# BpodMainBoard_r1_0.net
KiCad netlist of a schematic drawn in EAGLE
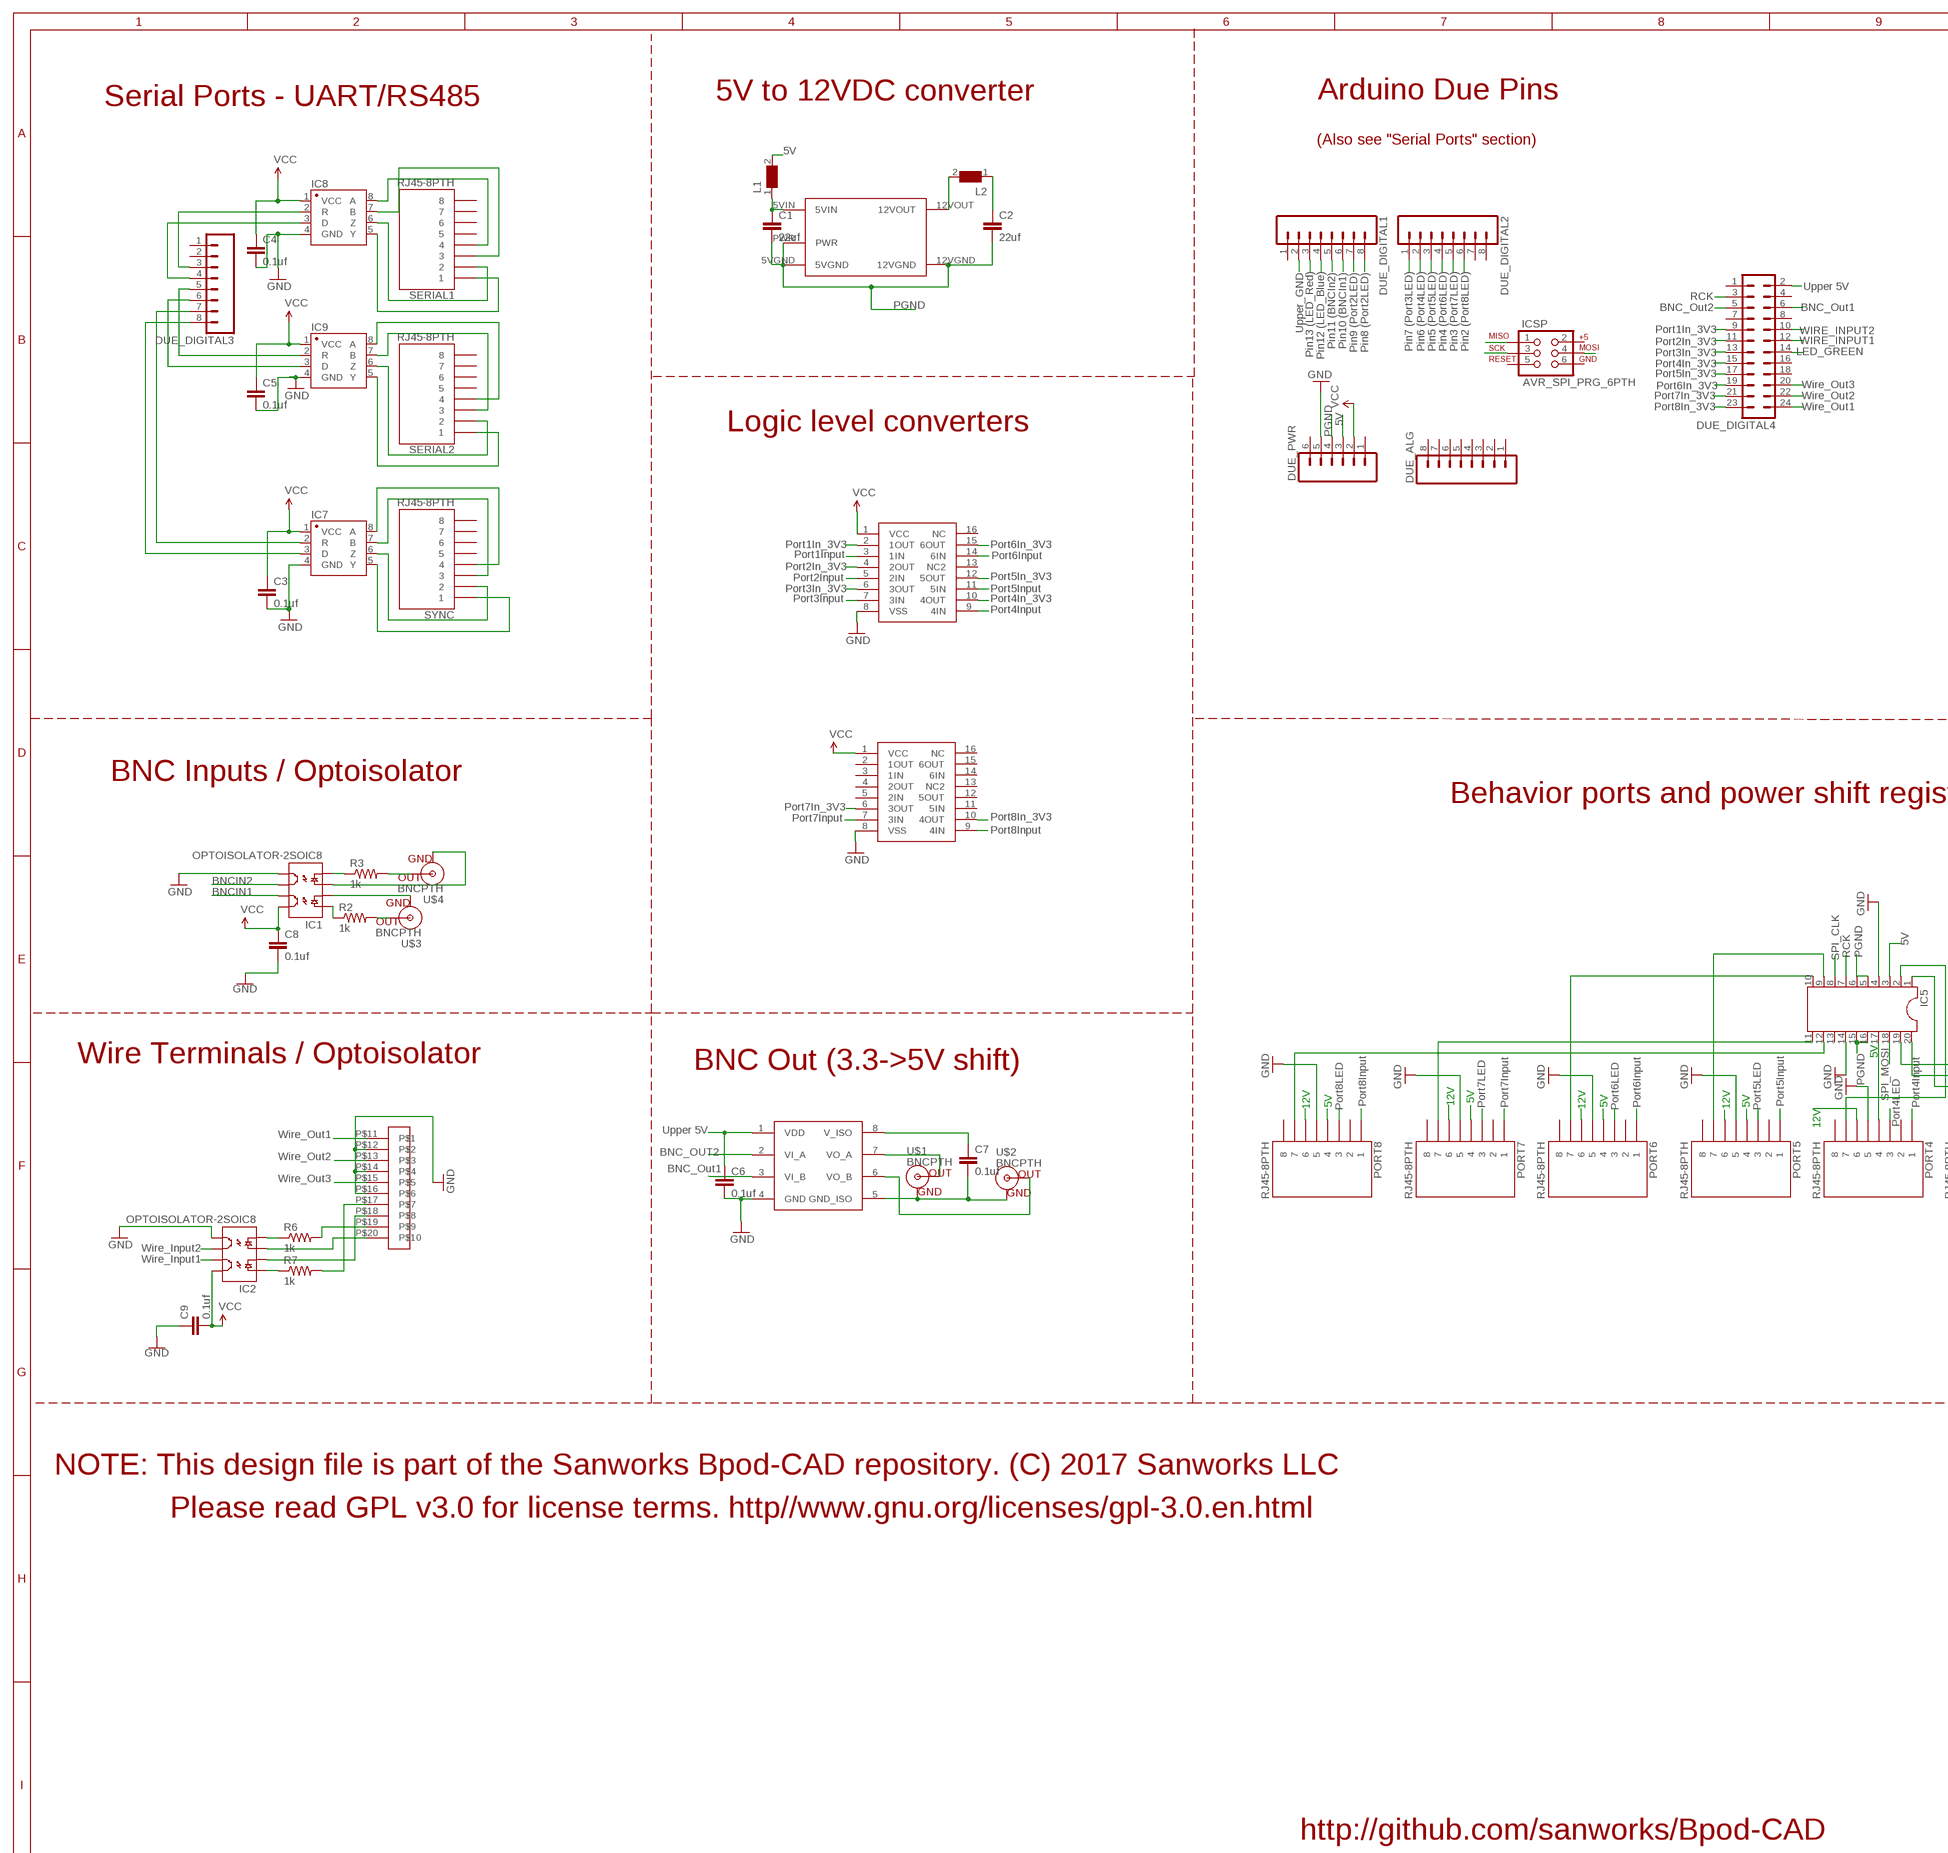
[diagram p0: schematic, sheet 1, part 1 of 2]
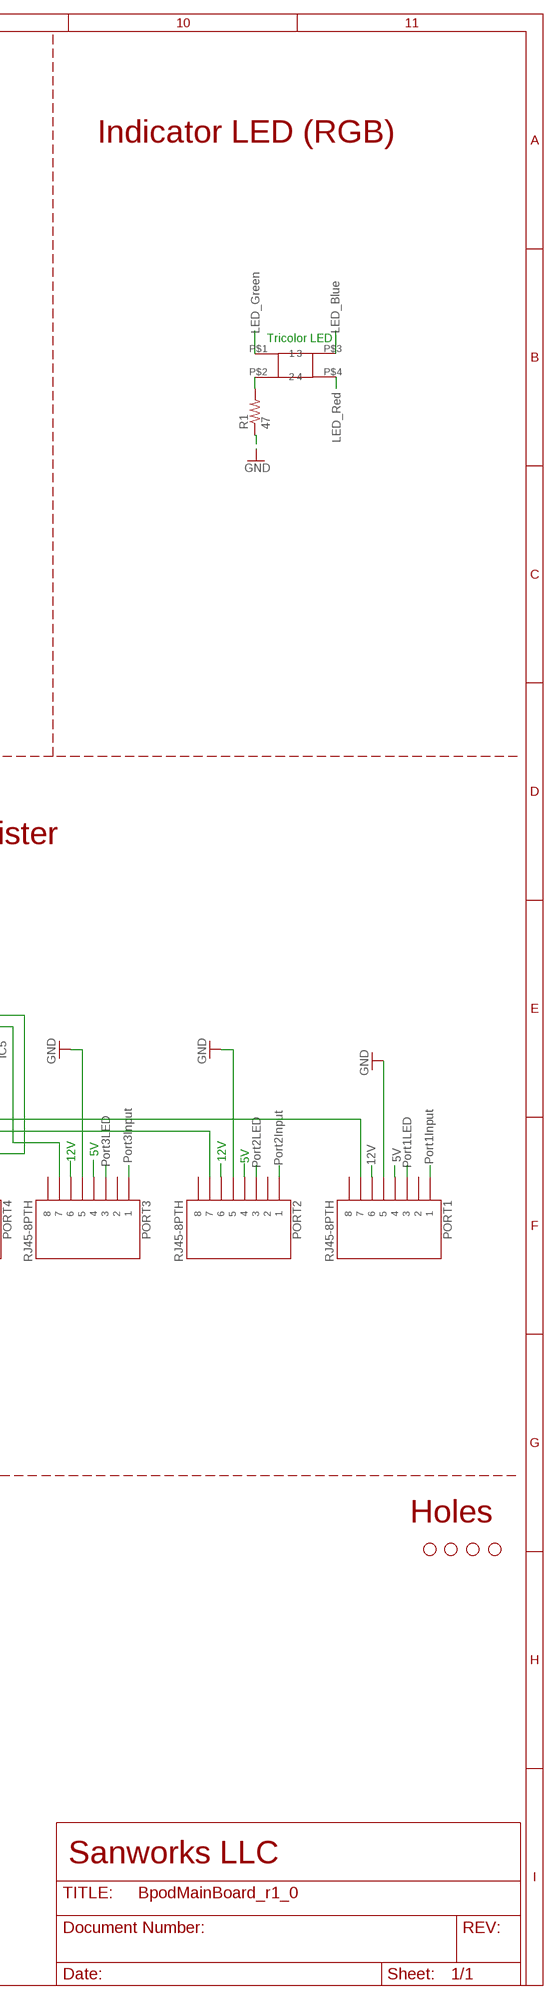
[diagram p1: schematic, sheet 1, part 2 of 2]

(export (version "E")
  (design (tool "Eeschema 10.0.6"))
  (components
    (comp (ref "C1")
      (value "22uf")
      (footprint "eagle-import:1206")
      (libsource (lib "eagle-import") (part "CAP1206"))
    )
    (comp (ref "C2")
      (value "22uf")
      (footprint "eagle-import:1206")
      (libsource (lib "eagle-import") (part "CAP1206"))
    )
    (comp (ref "C3")
      (value "0.1uf")
      (footprint "eagle-import:1206")
      (libsource (lib "eagle-import") (part "CAP1206"))
    )
    (comp (ref "C4")
      (value "0.1uf")
      (footprint "eagle-import:1206")
      (libsource (lib "eagle-import") (part "CAP1206"))
    )
    (comp (ref "C5")
      (value "0.1uf")
      (footprint "eagle-import:1206")
      (libsource (lib "eagle-import") (part "CAP1206"))
    )
    (comp (ref "C6")
      (value "0.1uf")
      (footprint "eagle-import:1206")
      (libsource (lib "eagle-import") (part "CAP1206"))
    )
    (comp (ref "C7")
      (value "0.1uf")
      (footprint "eagle-import:1206")
      (libsource (lib "eagle-import") (part "CAP1206"))
    )
    (comp (ref "C8")
      (value "0.1uf")
      (footprint "eagle-import:1206")
      (libsource (lib "eagle-import") (part "CAP1206"))
    )
    (comp (ref "C9")
      (value "0.1uf")
      (footprint "eagle-import:1206")
      (libsource (lib "eagle-import") (part "CAP1206"))
    )
    (comp (ref "DUE_ALG")
      (value "M081X08")
      (footprint "eagle-import:1X08")
      (libsource (lib "eagle-import") (part "M081X08"))
    )
    (comp (ref "DUE_DIGITAL1")
      (value "M081X08")
      (footprint "eagle-import:1X08")
      (libsource (lib "eagle-import") (part "M081X08"))
    )
    (comp (ref "DUE_DIGITAL2")
      (value "M081X08")
      (footprint "eagle-import:1X08")
      (libsource (lib "eagle-import") (part "M081X08"))
    )
    (comp (ref "DUE_DIGITAL3")
      (value "M081X08")
      (footprint "eagle-import:1X08")
      (libsource (lib "eagle-import") (part "M081X08"))
    )
    (comp (ref "DUE_DIGITAL4")
      (value "MA12-2")
      (footprint "eagle-import:MA12-2")
      (libsource (lib "eagle-import") (part "MA12-2"))
    )
    (comp (ref "DUE_PWR")
      (value "M06SIP")
      (footprint "eagle-import:1X06")
      (libsource (lib "eagle-import") (part "M06SIP"))
    )
    (comp (ref "IC1")
      (value "OPTOISOLATOR-2SOIC8")
      (footprint "eagle-import:SO08-2")
      (libsource (lib "eagle-import") (part "OPTOISOLATOR-2SOIC8"))
    )
    (comp (ref "IC2")
      (value "OPTOISOLATOR-2SOIC8")
      (footprint "eagle-import:SO08-2")
      (fields (field (name "PROD_ID") "IC-09076"))
      (libsource (lib "eagle-import") (part "OPTOISOLATOR-2SOIC8"))
    )
    (comp (ref "IC3")
      (value "CD4050")
      (footprint "eagle-import:SO16")
      (libsource (lib "eagle-import") (part "CD4050"))
    )
    (comp (ref "IC4")
      (value "CD4050")
      (footprint "eagle-import:SO16")
      (libsource (lib "eagle-import") (part "CD4050"))
    )
    (comp (ref "IC5")
      (value "DIL20")
      (footprint "eagle-import:DIL20")
      (libsource (lib "eagle-import") (part "DIL20"))
    )
    (comp (ref "IC7")
      (value "SN65HVD31DR")
      (footprint "eagle-import:SO08")
      (libsource (lib "eagle-import") (part "SN65HVD31DR"))
    )
    (comp (ref "IC8")
      (value "SN65HVD31DR")
      (footprint "eagle-import:SO08")
      (libsource (lib "eagle-import") (part "SN65HVD31DR"))
    )
    (comp (ref "IC9")
      (value "SN65HVD31DR")
      (footprint "eagle-import:SO08")
      (libsource (lib "eagle-import") (part "SN65HVD31DR"))
    )
    (comp (ref "IC10")
      (value "ADUM5240")
      (footprint "eagle-import:SO08")
      (libsource (lib "eagle-import") (part "ADUM5240"))
    )
    (comp (ref "ICSP")
      (value "AVR_SPI_PRG_6PTH")
      (footprint "eagle-import:2X3")
      (libsource (lib "eagle-import") (part "AVR_SPI_PRG_6PTH"))
    )
    (comp (ref "JP1")
      (value "STAND-OFF")
      (footprint "eagle-import:STAND-OFF")
      (libsource (lib "eagle-import") (part "STAND-OFF"))
    )
    (comp (ref "JP2")
      (value "STAND-OFF")
      (footprint "eagle-import:STAND-OFF")
      (libsource (lib "eagle-import") (part "STAND-OFF"))
    )
    (comp (ref "JP3")
      (value "STAND-OFF")
      (footprint "eagle-import:STAND-OFF")
      (libsource (lib "eagle-import") (part "STAND-OFF"))
    )
    (comp (ref "JP4")
      (value "STAND-OFF")
      (footprint "eagle-import:STAND-OFF")
      (libsource (lib "eagle-import") (part "STAND-OFF"))
    )
    (comp (ref "L1")
      (value "WE-CBF-742792118_1206")
      (footprint "eagle-import:1206")
      (fields (field (name "MPN") "742792118"))
      (libsource (lib "eagle-import") (part "WE-CBF_1206-742792118"))
    )
    (comp (ref "L2")
      (value "WE-CBF-742792118_1206")
      (footprint "eagle-import:1206")
      (fields
        (field (name "MPN") "742792118")
        (field (name "MPN_1") "742792118")
        (field (name "OC_FARNELL") "1800374")
        (field (name "OC_NEWARK") "78R5648")
        (field (name "PACKAGE") "IND-1206")
        (field (name "SUPPLIER") "Wuerth Elektronik")
      )
      (libsource (lib "eagle-import") (part "WE-CBF_1206-742792118"))
    )
    (comp (ref "PORT1")
      (value "RJ45-8PTH")
      (footprint "eagle-import:RJ45-8")
      (libsource (lib "eagle-import") (part "RJ45-8PTH"))
    )
    (comp (ref "PORT2")
      (value "RJ45-8PTH")
      (footprint "eagle-import:RJ45-8")
      (libsource (lib "eagle-import") (part "RJ45-8PTH"))
    )
    (comp (ref "PORT3")
      (value "RJ45-8PTH")
      (footprint "eagle-import:RJ45-8")
      (libsource (lib "eagle-import") (part "RJ45-8PTH"))
    )
    (comp (ref "PORT4")
      (value "RJ45-8PTH")
      (footprint "eagle-import:RJ45-8")
      (libsource (lib "eagle-import") (part "RJ45-8PTH"))
    )
    (comp (ref "PORT5")
      (value "RJ45-8PTH")
      (footprint "eagle-import:RJ45-8")
      (libsource (lib "eagle-import") (part "RJ45-8PTH"))
    )
    (comp (ref "PORT6")
      (value "RJ45-8PTH")
      (footprint "eagle-import:RJ45-8")
      (libsource (lib "eagle-import") (part "RJ45-8PTH"))
    )
    (comp (ref "PORT7")
      (value "RJ45-8PTH")
      (footprint "eagle-import:RJ45-8")
      (libsource (lib "eagle-import") (part "RJ45-8PTH"))
    )
    (comp (ref "PORT8")
      (value "RJ45-8PTH")
      (footprint "eagle-import:RJ45-8")
      (libsource (lib "eagle-import") (part "RJ45-8PTH"))
    )
    (comp (ref "R1")
      (value "47")
      (footprint "eagle-import:1206")
      (libsource (lib "eagle-import") (part "RESISTOR1206"))
    )
    (comp (ref "R2")
      (value "1k")
      (footprint "eagle-import:1206")
      (libsource (lib "eagle-import") (part "SparkFun-Resistors_RESISTOR1206"))
    )
    (comp (ref "R3")
      (value "1k")
      (footprint "eagle-import:1206")
      (libsource (lib "eagle-import") (part "SparkFun-Resistors_RESISTOR1206"))
    )
    (comp (ref "R6")
      (value "1k")
      (footprint "eagle-import:1206")
      (libsource (lib "eagle-import") (part "SparkFun-Resistors_RESISTOR1206"))
    )
    (comp (ref "R7")
      (value "1k")
      (footprint "eagle-import:1206")
      (libsource (lib "eagle-import") (part "SparkFun-Resistors_RESISTOR1206"))
    )
    (comp (ref "SERIAL1")
      (value "RJ45-8PTH")
      (footprint "eagle-import:RJ45-8")
      (libsource (lib "eagle-import") (part "RJ45-8PTH"))
    )
    (comp (ref "SERIAL2")
      (value "RJ45-8PTH")
      (footprint "eagle-import:RJ45-8")
      (libsource (lib "eagle-import") (part "RJ45-8PTH"))
    )
    (comp (ref "SYNC")
      (value "RJ45-8PTH")
      (footprint "eagle-import:RJ45-8")
      (libsource (lib "eagle-import") (part "RJ45-8PTH"))
    )
    (comp (ref "U$1")
      (value "BNCPTH")
      (footprint "eagle-import:BNC")
      (libsource (lib "eagle-import") (part "SparkFun-Connectors_BNCPTH"))
    )
    (comp (ref "U$2")
      (value "BNCPTH")
      (footprint "eagle-import:BNC")
      (libsource (lib "eagle-import") (part "SparkFun-Connectors_BNCPTH"))
    )
    (comp (ref "U$3")
      (value "BNCPTH")
      (footprint "eagle-import:BNC")
      (libsource (lib "eagle-import") (part "BNCPTH"))
    )
    (comp (ref "U$4")
      (value "BNCPTH")
      (footprint "eagle-import:BNC")
      (libsource (lib "eagle-import") (part "BNCPTH"))
    )
    (comp (ref "U$5")
      (value "TDK_LAMBDA_5V_TO_12V")
      (footprint "eagle-import:TDK_LAMBDA_5V_12V")
      (libsource (lib "eagle-import") (part "TDK_LAMBDA_5V_TO_12V"))
    )
    (comp (ref "U$6")
      (value "10POS_SPRING_TERMINAL")
      (footprint "eagle-import:10POS_SCREW_TERMINAL")
      (libsource (lib "eagle-import") (part "10POS_SPRING_TERMINAL"))
    )
    (comp (ref "U$8")
      (value "SQUARE_TRICOLOR_LED")
      (footprint "eagle-import:SQUARE_TRICOLOR_LED")
      (libsource (lib "eagle-import") (part "SQUARE_TRICOLOR_LED"))
    )
  )
  (nets
    (net (code "1") (name "/5V") (class "Default")
      (node (ref "DUE_PWR") (pin "3") (pinfunction "3_3") (pintype "passive"))
      (node (ref "IC5") (pin "17") (pinfunction "17_17") (pintype "passive"))
      (node (ref "IC5") (pin "3") (pinfunction "3_3") (pintype "passive"))
      (node (ref "L1") (pin "2") (pinfunction "2_2") (pintype "passive"))
      (node (ref "PORT1") (pin "4") (pinfunction "4_4") (pintype "bidirectional"))
      (node (ref "PORT2") (pin "4") (pinfunction "4_4") (pintype "bidirectional"))
      (node (ref "PORT3") (pin "4") (pinfunction "4_4") (pintype "bidirectional"))
      (node (ref "PORT4") (pin "4") (pinfunction "4_4") (pintype "bidirectional"))
      (node (ref "PORT5") (pin "4") (pinfunction "4_4") (pintype "bidirectional"))
      (node (ref "PORT6") (pin "4") (pinfunction "4_4") (pintype "bidirectional"))
      (node (ref "PORT7") (pin "4") (pinfunction "4_4") (pintype "bidirectional"))
      (node (ref "PORT8") (pin "4") (pinfunction "4_4") (pintype "bidirectional"))
    )
    (net (code "2") (name "/12V") (class "Default")
      (node (ref "C2") (pin "1") (pinfunction "1_1") (pintype "passive"))
      (node (ref "L2") (pin "1") (pinfunction "1_1") (pintype "passive"))
      (node (ref "PORT1") (pin "6") (pinfunction "6_6") (pintype "bidirectional"))
      (node (ref "PORT2") (pin "6") (pinfunction "6_6") (pintype "bidirectional"))
      (node (ref "PORT3") (pin "6") (pinfunction "6_6") (pintype "bidirectional"))
      (node (ref "PORT4") (pin "6") (pinfunction "6_6") (pintype "bidirectional"))
      (node (ref "PORT5") (pin "6") (pinfunction "6_6") (pintype "bidirectional"))
      (node (ref "PORT6") (pin "6") (pinfunction "6_6") (pintype "bidirectional"))
      (node (ref "PORT7") (pin "6") (pinfunction "6_6") (pintype "bidirectional"))
      (node (ref "PORT8") (pin "6") (pinfunction "6_6") (pintype "bidirectional"))
    )
    (net (code "3") (name "/BNCIN1") (class "Default")
      (node (ref "DUE_DIGITAL1") (pin "6") (pinfunction "6_6") (pintype "passive"))
      (node (ref "IC1") (pin "7") (pinfunction "EM1_7") (pintype "bidirectional"))
    )
    (net (code "4") (name "/BNCIN2") (class "Default")
      (node (ref "DUE_DIGITAL1") (pin "5") (pinfunction "5_5") (pintype "passive"))
      (node (ref "IC1") (pin "6") (pinfunction "CL2_6") (pintype "bidirectional"))
    )
    (net (code "5") (name "/BNC_OUT1") (class "Default")
      (node (ref "DUE_DIGITAL4") (pin "6") (pinfunction "6_6") (pintype "passive"))
      (node (ref "IC10") (pin "3") (pinfunction "VI_B_3") (pintype "bidirectional"))
    )
    (net (code "6") (name "/BNC_OUT2") (class "Default")
      (node (ref "DUE_DIGITAL4") (pin "5") (pinfunction "5_5") (pintype "passive"))
      (node (ref "IC10") (pin "2") (pinfunction "VI_A_2") (pintype "bidirectional"))
    )
    (net (code "7") (name "/LED_BLUE") (class "Default")
      (node (ref "DUE_DIGITAL1") (pin "4") (pinfunction "4_4") (pintype "passive"))
      (node (ref "U$8") (pin "P$3") (pinfunction "3_P$3") (pintype "bidirectional"))
    )
    (net (code "8") (name "/LED_GREEN") (class "Default")
      (node (ref "DUE_DIGITAL4") (pin "14") (pinfunction "14_14") (pintype "passive"))
      (node (ref "U$8") (pin "P$1") (pinfunction "1_P$1") (pintype "bidirectional"))
    )
    (net (code "9") (name "/LED_RED") (class "Default")
      (node (ref "DUE_DIGITAL1") (pin "3") (pinfunction "3_3") (pintype "passive"))
      (node (ref "U$8") (pin "P$4") (pinfunction "4_P$4") (pintype "bidirectional"))
    )
    (net (code "10") (name "/MOSI") (class "Default")
      (node (ref "IC5") (pin "18") (pinfunction "18_18") (pintype "passive"))
      (node (ref "ICSP") (pin "4") (pinfunction "4_4") (pintype "passive"))
    )
    (net (code "11") (name "/PGND") (class "Default")
      (node (ref "C1") (pin "2") (pinfunction "2_2") (pintype "passive"))
      (node (ref "C2") (pin "2") (pinfunction "2_2") (pintype "passive"))
      (node (ref "DUE_PWR") (pin "4") (pinfunction "4_4") (pintype "passive"))
      (node (ref "IC5") (pin "15") (pinfunction "15_15") (pintype "passive"))
      (node (ref "IC5") (pin "16") (pinfunction "16_16") (pintype "passive"))
      (node (ref "IC5") (pin "5") (pinfunction "5_5") (pintype "passive"))
      (node (ref "IC5") (pin "6") (pinfunction "6_6") (pintype "passive"))
      (node (ref "U$5") (pin "12VGND") (pinfunction "12VGND_12VGND") (pintype "bidirectional"))
      (node (ref "U$5") (pin "5VGND") (pinfunction "5VGND_5VGND") (pintype "bidirectional"))
      (node (ref "U$5") (pin "PWR") (pinfunction "PWR_PWR") (pintype "bidirectional"))
    )
    (net (code "12") (name "/PORT1INPUT") (class "Default")
      (node (ref "IC3") (pin "3") (pinfunction "1IN_3") (pintype "bidirectional"))
      (node (ref "PORT1") (pin "1") (pinfunction "1_1") (pintype "bidirectional"))
    )
    (net (code "13") (name "/PORT1IN_3V3") (class "Default")
      (node (ref "DUE_DIGITAL4") (pin "9") (pinfunction "9_9") (pintype "passive"))
      (node (ref "IC3") (pin "2") (pinfunction "1OUT_2") (pintype "bidirectional"))
    )
    (net (code "14") (name "/PORT1LED") (class "Default")
      (node (ref "DUE_DIGITAL1") (pin "7") (pinfunction "7_7") (pintype "passive"))
      (node (ref "PORT1") (pin "3") (pinfunction "3_3") (pintype "bidirectional"))
    )
    (net (code "15") (name "/PORT2INPUT") (class "Default")
      (node (ref "IC3") (pin "5") (pinfunction "2IN_5") (pintype "bidirectional"))
      (node (ref "PORT2") (pin "1") (pinfunction "1_1") (pintype "bidirectional"))
    )
    (net (code "16") (name "/PORT2IN_3V3") (class "Default")
      (node (ref "DUE_DIGITAL4") (pin "11") (pinfunction "11_11") (pintype "passive"))
      (node (ref "IC3") (pin "4") (pinfunction "2OUT_4") (pintype "bidirectional"))
    )
    (net (code "17") (name "/PORT2LED") (class "Default")
      (node (ref "DUE_DIGITAL1") (pin "8") (pinfunction "8_8") (pintype "passive"))
      (node (ref "PORT2") (pin "3") (pinfunction "3_3") (pintype "bidirectional"))
    )
    (net (code "18") (name "/PORT3INPUT") (class "Default")
      (node (ref "IC3") (pin "7") (pinfunction "3IN_7") (pintype "bidirectional"))
      (node (ref "PORT3") (pin "1") (pinfunction "1_1") (pintype "bidirectional"))
    )
    (net (code "19") (name "/PORT3IN_3V3") (class "Default")
      (node (ref "DUE_DIGITAL4") (pin "13") (pinfunction "13_13") (pintype "passive"))
      (node (ref "IC3") (pin "6") (pinfunction "3OUT_6") (pintype "bidirectional"))
    )
    (net (code "20") (name "/PORT3LED") (class "Default")
      (node (ref "DUE_DIGITAL2") (pin "1") (pinfunction "1_1") (pintype "passive"))
      (node (ref "PORT3") (pin "3") (pinfunction "3_3") (pintype "bidirectional"))
    )
    (net (code "21") (name "/PORT4INPUT") (class "Default")
      (node (ref "IC3") (pin "9") (pinfunction "4IN_9") (pintype "bidirectional"))
      (node (ref "PORT4") (pin "1") (pinfunction "1_1") (pintype "bidirectional"))
    )
    (net (code "22") (name "/PORT4IN_3V3") (class "Default")
      (node (ref "DUE_DIGITAL4") (pin "15") (pinfunction "15_15") (pintype "passive"))
      (node (ref "IC3") (pin "10") (pinfunction "4OUT_10") (pintype "bidirectional"))
    )
    (net (code "23") (name "/PORT4LED") (class "Default")
      (node (ref "DUE_DIGITAL2") (pin "2") (pinfunction "2_2") (pintype "passive"))
      (node (ref "PORT4") (pin "3") (pinfunction "3_3") (pintype "bidirectional"))
    )
    (net (code "24") (name "/PORT5INPUT") (class "Default")
      (node (ref "IC3") (pin "11") (pinfunction "5IN_11") (pintype "bidirectional"))
      (node (ref "PORT5") (pin "1") (pinfunction "1_1") (pintype "bidirectional"))
    )
    (net (code "25") (name "/PORT5IN_3V3") (class "Default")
      (node (ref "DUE_DIGITAL4") (pin "17") (pinfunction "17_17") (pintype "passive"))
      (node (ref "IC3") (pin "12") (pinfunction "5OUT_12") (pintype "bidirectional"))
    )
    (net (code "26") (name "/PORT5LED") (class "Default")
      (node (ref "DUE_DIGITAL2") (pin "3") (pinfunction "3_3") (pintype "passive"))
      (node (ref "PORT5") (pin "3") (pinfunction "3_3") (pintype "bidirectional"))
    )
    (net (code "27") (name "/PORT6INPUT") (class "Default")
      (node (ref "IC3") (pin "14") (pinfunction "6IN_14") (pintype "bidirectional"))
      (node (ref "PORT6") (pin "1") (pinfunction "1_1") (pintype "bidirectional"))
    )
    (net (code "28") (name "/PORT6IN_3V3") (class "Default")
      (node (ref "DUE_DIGITAL4") (pin "19") (pinfunction "19_19") (pintype "passive"))
      (node (ref "IC3") (pin "15") (pinfunction "6OUT_15") (pintype "bidirectional"))
    )
    (net (code "29") (name "/PORT6LED") (class "Default")
      (node (ref "DUE_DIGITAL2") (pin "4") (pinfunction "4_4") (pintype "passive"))
      (node (ref "PORT6") (pin "3") (pinfunction "3_3") (pintype "bidirectional"))
    )
    (net (code "30") (name "/PORT7INPUT") (class "Default")
      (node (ref "IC4") (pin "7") (pinfunction "3IN_7") (pintype "bidirectional"))
      (node (ref "PORT7") (pin "1") (pinfunction "1_1") (pintype "bidirectional"))
    )
    (net (code "31") (name "/PORT7IN_3V3") (class "Default")
      (node (ref "DUE_DIGITAL4") (pin "21") (pinfunction "21_21") (pintype "passive"))
      (node (ref "IC4") (pin "6") (pinfunction "3OUT_6") (pintype "bidirectional"))
    )
    (net (code "32") (name "/PORT7LED") (class "Default")
      (node (ref "DUE_DIGITAL2") (pin "5") (pinfunction "5_5") (pintype "passive"))
      (node (ref "PORT7") (pin "3") (pinfunction "3_3") (pintype "bidirectional"))
    )
    (net (code "33") (name "/PORT8INPUT") (class "Default")
      (node (ref "IC4") (pin "9") (pinfunction "4IN_9") (pintype "bidirectional"))
      (node (ref "PORT8") (pin "1") (pinfunction "1_1") (pintype "bidirectional"))
    )
    (net (code "34") (name "/PORT8IN_3V3") (class "Default")
      (node (ref "DUE_DIGITAL4") (pin "23") (pinfunction "23_23") (pintype "passive"))
      (node (ref "IC4") (pin "10") (pinfunction "4OUT_10") (pintype "bidirectional"))
    )
    (net (code "35") (name "/PORT8LED") (class "Default")
      (node (ref "DUE_DIGITAL2") (pin "6") (pinfunction "6_6") (pintype "passive"))
      (node (ref "PORT8") (pin "3") (pinfunction "3_3") (pintype "bidirectional"))
    )
    (net (code "36") (name "/RCK") (class "Default")
      (node (ref "DUE_DIGITAL4") (pin "3") (pinfunction "3_3") (pintype "passive"))
      (node (ref "IC5") (pin "7") (pinfunction "7_7") (pintype "passive"))
    )
    (net (code "37") (name "/SPI_CLK") (class "Default")
      (node (ref "IC5") (pin "8") (pinfunction "8_8") (pintype "passive"))
      (node (ref "ICSP") (pin "3") (pinfunction "3_3") (pintype "passive"))
    )
    (net (code "38") (name "/UPPER_5V") (class "Default")
      (node (ref "C6") (pin "1") (pinfunction "1_1") (pintype "passive"))
      (node (ref "DUE_DIGITAL4") (pin "2") (pinfunction "2_2") (pintype "passive"))
      (node (ref "IC10") (pin "1") (pinfunction "VDD_1") (pintype "bidirectional"))
    )
    (net (code "39") (name "/WIREOUT3") (class "Default")
      (node (ref "DUE_DIGITAL4") (pin "20") (pinfunction "20_20") (pintype "passive"))
      (node (ref "U$6") (pin "P$15") (pinfunction "P$5_P$15") (pintype "bidirectional"))
    )
    (net (code "40") (name "/WIRE_INPUT1") (class "Default")
      (node (ref "DUE_DIGITAL4") (pin "12") (pinfunction "12_12") (pintype "passive"))
      (node (ref "IC2") (pin "7") (pinfunction "EM1_7") (pintype "bidirectional"))
    )
    (net (code "41") (name "/WIRE_INPUT2") (class "Default")
      (node (ref "DUE_DIGITAL4") (pin "10") (pinfunction "10_10") (pintype "passive"))
      (node (ref "IC2") (pin "6") (pinfunction "CL2_6") (pintype "bidirectional"))
    )
    (net (code "42") (name "/WIRE_OUT1") (class "Default")
      (node (ref "DUE_DIGITAL4") (pin "24") (pinfunction "24_24") (pintype "passive"))
      (node (ref "U$6") (pin "P$11") (pinfunction "P$1_P$11") (pintype "bidirectional"))
    )
    (net (code "43") (name "/WIRE_OUT2") (class "Default")
      (node (ref "DUE_DIGITAL4") (pin "22") (pinfunction "22_22") (pintype "passive"))
      (node (ref "U$6") (pin "P$13") (pinfunction "P$3_P$13") (pintype "bidirectional"))
    )
    (net (code "44") (name "GND") (class "Default")
      (node (ref "C3") (pin "2") (pinfunction "2_2") (pintype "passive"))
      (node (ref "C4") (pin "2") (pinfunction "2_2") (pintype "passive"))
      (node (ref "C5") (pin "2") (pinfunction "2_2") (pintype "passive"))
      (node (ref "C6") (pin "2") (pinfunction "2_2") (pintype "passive"))
      (node (ref "C8") (pin "2") (pinfunction "2_2") (pintype "passive"))
      (node (ref "C9") (pin "1") (pinfunction "1_1") (pintype "passive"))
      (node (ref "DUE_PWR") (pin "5") (pinfunction "5_5") (pintype "passive"))
      (node (ref "IC1") (pin "5") (pinfunction "EM2_5") (pintype "bidirectional"))
      (node (ref "IC10") (pin "4") (pinfunction "GND_4") (pintype "bidirectional"))
      (node (ref "IC2") (pin "5") (pinfunction "EM2_5") (pintype "bidirectional"))
      (node (ref "IC3") (pin "8") (pinfunction "VSS_8") (pintype "bidirectional"))
      (node (ref "IC4") (pin "8") (pinfunction "VSS_8") (pintype "bidirectional"))
      (node (ref "IC5") (pin "14") (pinfunction "14_14") (pintype "passive"))
      (node (ref "IC5") (pin "4") (pinfunction "4_4") (pintype "passive"))
      (node (ref "IC7") (pin "4") (pinfunction "GND_4") (pintype "bidirectional"))
      (node (ref "IC8") (pin "4") (pinfunction "GND_4") (pintype "bidirectional"))
      (node (ref "IC9") (pin "4") (pinfunction "GND_4") (pintype "bidirectional"))
      (node (ref "PORT1") (pin "5") (pinfunction "5_5") (pintype "bidirectional"))
      (node (ref "PORT2") (pin "5") (pinfunction "5_5") (pintype "bidirectional"))
      (node (ref "PORT3") (pin "5") (pinfunction "5_5") (pintype "bidirectional"))
      (node (ref "PORT4") (pin "5") (pinfunction "5_5") (pintype "bidirectional"))
      (node (ref "PORT5") (pin "5") (pinfunction "5_5") (pintype "bidirectional"))
      (node (ref "PORT6") (pin "5") (pinfunction "5_5") (pintype "bidirectional"))
      (node (ref "PORT7") (pin "5") (pinfunction "5_5") (pintype "bidirectional"))
      (node (ref "PORT8") (pin "5") (pinfunction "5_5") (pintype "bidirectional"))
      (node (ref "R1") (pin "1") (pinfunction "1_1") (pintype "passive"))
      (node (ref "U$6") (pin "P$12") (pinfunction "P$2_P$12") (pintype "bidirectional"))
      (node (ref "U$6") (pin "P$14") (pinfunction "P$4_P$14") (pintype "bidirectional"))
      (node (ref "U$6") (pin "P$16") (pinfunction "P$6_P$16") (pintype "bidirectional"))
    )
    (net (code "45") (name "Net-(C1-Pad1)") (class "Default")
      (node (ref "C1") (pin "1") (pinfunction "1_1") (pintype "passive"))
      (node (ref "L1") (pin "1") (pinfunction "1_1") (pintype "passive"))
      (node (ref "U$5") (pin "5VIN") (pinfunction "5VIN_5VIN") (pintype "bidirectional"))
    )
    (net (code "46") (name "Net-(IC1-A1)") (class "Default")
      (node (ref "IC1") (pin "1") (pinfunction "A1_1") (pintype "bidirectional"))
      (node (ref "R2") (pin "1") (pinfunction "1_1") (pintype "passive"))
    )
    (net (code "47") (name "Net-(IC1-A2)") (class "Default")
      (node (ref "IC1") (pin "3") (pinfunction "A2_3") (pintype "bidirectional"))
      (node (ref "U$4") (pin "GND") (pinfunction "GND_GND") (pintype "bidirectional"))
    )
    (net (code "48") (name "Net-(IC1-C1)") (class "Default")
      (node (ref "IC1") (pin "2") (pinfunction "C1_2") (pintype "bidirectional"))
      (node (ref "U$3") (pin "GND") (pinfunction "GND_GND") (pintype "bidirectional"))
    )
    (net (code "49") (name "Net-(IC1-C2)") (class "Default")
      (node (ref "IC1") (pin "4") (pinfunction "C2_4") (pintype "bidirectional"))
      (node (ref "R3") (pin "1") (pinfunction "1_1") (pintype "passive"))
    )
    (net (code "50") (name "Net-(IC2-A1)") (class "Default")
      (node (ref "IC2") (pin "1") (pinfunction "A1_1") (pintype "bidirectional"))
      (node (ref "R7") (pin "1") (pinfunction "1_1") (pintype "passive"))
    )
    (net (code "51") (name "Net-(IC2-A2)") (class "Default")
      (node (ref "IC2") (pin "3") (pinfunction "A2_3") (pintype "bidirectional"))
      (node (ref "U$6") (pin "P$20") (pinfunction "P$10_P$20") (pintype "bidirectional"))
    )
    (net (code "52") (name "Net-(IC2-C1)") (class "Default")
      (node (ref "IC2") (pin "2") (pinfunction "C1_2") (pintype "bidirectional"))
      (node (ref "U$6") (pin "P$18") (pinfunction "P$8_P$18") (pintype "bidirectional"))
    )
    (net (code "53") (name "Net-(IC2-C2)") (class "Default")
      (node (ref "IC2") (pin "4") (pinfunction "C2_4") (pintype "bidirectional"))
      (node (ref "R6") (pin "1") (pinfunction "1_1") (pintype "passive"))
    )
    (net (code "54") (name "Net-(IC5-Pad1)") (class "Default")
      (node (ref "IC5") (pin "1") (pinfunction "1_1") (pintype "passive"))
      (node (ref "PORT3") (pin "7") (pinfunction "7_7") (pintype "bidirectional"))
    )
    (net (code "55") (name "Net-(IC5-Pad2)") (class "Default")
      (node (ref "IC5") (pin "2") (pinfunction "2_2") (pintype "passive"))
      (node (ref "PORT4") (pin "7") (pinfunction "7_7") (pintype "bidirectional"))
    )
    (net (code "56") (name "Net-(IC5-Pad9)") (class "Default")
      (node (ref "IC5") (pin "9") (pinfunction "9_9") (pintype "passive"))
      (node (ref "PORT5") (pin "7") (pinfunction "7_7") (pintype "bidirectional"))
    )
    (net (code "57") (name "Net-(IC5-Pad10)") (class "Default")
      (node (ref "IC5") (pin "10") (pinfunction "10_10") (pintype "passive"))
      (node (ref "PORT6") (pin "7") (pinfunction "7_7") (pintype "bidirectional"))
    )
    (net (code "58") (name "Net-(IC5-Pad11)") (class "Default")
      (node (ref "IC5") (pin "11") (pinfunction "11_11") (pintype "passive"))
      (node (ref "PORT7") (pin "7") (pinfunction "7_7") (pintype "bidirectional"))
    )
    (net (code "59") (name "Net-(IC5-Pad12)") (class "Default")
      (node (ref "IC5") (pin "12") (pinfunction "12_12") (pintype "passive"))
      (node (ref "PORT8") (pin "7") (pinfunction "7_7") (pintype "bidirectional"))
    )
    (net (code "60") (name "Net-(IC5-Pad19)") (class "Default")
      (node (ref "IC5") (pin "19") (pinfunction "19_19") (pintype "passive"))
      (node (ref "PORT1") (pin "7") (pinfunction "7_7") (pintype "bidirectional"))
    )
    (net (code "61") (name "Net-(IC5-Pad20)") (class "Default")
      (node (ref "IC5") (pin "20") (pinfunction "20_20") (pintype "passive"))
      (node (ref "PORT2") (pin "7") (pinfunction "7_7") (pintype "bidirectional"))
    )
    (net (code "62") (name "Net-(IC7-A)") (class "Default")
      (node (ref "IC7") (pin "8") (pinfunction "A_8") (pintype "bidirectional"))
      (node (ref "SYNC") (pin "4") (pinfunction "4_4") (pintype "bidirectional"))
    )
    (net (code "63") (name "Net-(IC7-B)") (class "Default")
      (node (ref "IC7") (pin "7") (pinfunction "B_7") (pintype "bidirectional"))
      (node (ref "SYNC") (pin "3") (pinfunction "3_3") (pintype "bidirectional"))
    )
    (net (code "64") (name "Net-(IC7-D)") (class "Default")
      (node (ref "DUE_DIGITAL3") (pin "8") (pinfunction "8_8") (pintype "passive"))
      (node (ref "IC7") (pin "3") (pinfunction "D_3") (pintype "bidirectional"))
    )
    (net (code "65") (name "Net-(IC7-R)") (class "Default")
      (node (ref "DUE_DIGITAL3") (pin "7") (pinfunction "7_7") (pintype "passive"))
      (node (ref "IC7") (pin "2") (pinfunction "R_2") (pintype "bidirectional"))
    )
    (net (code "66") (name "Net-(IC7-Y)") (class "Default")
      (node (ref "IC7") (pin "5") (pinfunction "Y_5") (pintype "bidirectional"))
      (node (ref "SYNC") (pin "1") (pinfunction "1_1") (pintype "bidirectional"))
    )
    (net (code "67") (name "Net-(IC7-Z)") (class "Default")
      (node (ref "IC7") (pin "6") (pinfunction "Z_6") (pintype "bidirectional"))
      (node (ref "SYNC") (pin "2") (pinfunction "2_2") (pintype "bidirectional"))
    )
    (net (code "68") (name "Net-(IC8-A)") (class "Default")
      (node (ref "IC8") (pin "8") (pinfunction "A_8") (pintype "bidirectional"))
      (node (ref "SERIAL1") (pin "4") (pinfunction "4_4") (pintype "bidirectional"))
    )
    (net (code "69") (name "Net-(IC8-B)") (class "Default")
      (node (ref "IC8") (pin "7") (pinfunction "B_7") (pintype "bidirectional"))
      (node (ref "SERIAL1") (pin "3") (pinfunction "3_3") (pintype "bidirectional"))
    )
    (net (code "70") (name "Net-(IC8-D)") (class "Default")
      (node (ref "DUE_DIGITAL3") (pin "4") (pinfunction "4_4") (pintype "passive"))
      (node (ref "IC8") (pin "3") (pinfunction "D_3") (pintype "bidirectional"))
    )
    (net (code "71") (name "Net-(IC8-R)") (class "Default")
      (node (ref "DUE_DIGITAL3") (pin "3") (pinfunction "3_3") (pintype "passive"))
      (node (ref "IC8") (pin "2") (pinfunction "R_2") (pintype "bidirectional"))
    )
    (net (code "72") (name "Net-(IC8-Y)") (class "Default")
      (node (ref "IC8") (pin "5") (pinfunction "Y_5") (pintype "bidirectional"))
      (node (ref "SERIAL1") (pin "1") (pinfunction "1_1") (pintype "bidirectional"))
    )
    (net (code "73") (name "Net-(IC8-Z)") (class "Default")
      (node (ref "IC8") (pin "6") (pinfunction "Z_6") (pintype "bidirectional"))
      (node (ref "SERIAL1") (pin "2") (pinfunction "2_2") (pintype "bidirectional"))
    )
    (net (code "74") (name "Net-(IC9-A)") (class "Default")
      (node (ref "IC9") (pin "8") (pinfunction "A_8") (pintype "bidirectional"))
      (node (ref "SERIAL2") (pin "4") (pinfunction "4_4") (pintype "bidirectional"))
    )
    (net (code "75") (name "Net-(IC9-B)") (class "Default")
      (node (ref "IC9") (pin "7") (pinfunction "B_7") (pintype "bidirectional"))
      (node (ref "SERIAL2") (pin "3") (pinfunction "3_3") (pintype "bidirectional"))
    )
    (net (code "76") (name "Net-(IC9-D)") (class "Default")
      (node (ref "DUE_DIGITAL3") (pin "6") (pinfunction "6_6") (pintype "passive"))
      (node (ref "IC9") (pin "3") (pinfunction "D_3") (pintype "bidirectional"))
    )
    (net (code "77") (name "Net-(IC9-R)") (class "Default")
      (node (ref "DUE_DIGITAL3") (pin "5") (pinfunction "5_5") (pintype "passive"))
      (node (ref "IC9") (pin "2") (pinfunction "R_2") (pintype "bidirectional"))
    )
    (net (code "78") (name "Net-(IC9-Y)") (class "Default")
      (node (ref "IC9") (pin "5") (pinfunction "Y_5") (pintype "bidirectional"))
      (node (ref "SERIAL2") (pin "1") (pinfunction "1_1") (pintype "bidirectional"))
    )
    (net (code "79") (name "Net-(IC9-Z)") (class "Default")
      (node (ref "IC9") (pin "6") (pinfunction "Z_6") (pintype "bidirectional"))
      (node (ref "SERIAL2") (pin "2") (pinfunction "2_2") (pintype "bidirectional"))
    )
    (net (code "80") (name "Net-(IC10-GND_ISO)") (class "Default")
      (node (ref "C7") (pin "2") (pinfunction "2_2") (pintype "passive"))
      (node (ref "IC10") (pin "5") (pinfunction "GND_ISO_5") (pintype "bidirectional"))
      (node (ref "U$1") (pin "GND") (pinfunction "GND_GND") (pintype "bidirectional"))
      (node (ref "U$2") (pin "GND") (pinfunction "GND_GND") (pintype "bidirectional"))
    )
    (net (code "81") (name "Net-(IC10-VO_A)") (class "Default")
      (node (ref "IC10") (pin "7") (pinfunction "VO_A_7") (pintype "bidirectional"))
      (node (ref "U$1") (pin "S") (pinfunction "OUT_S") (pintype "bidirectional"))
    )
    (net (code "82") (name "Net-(IC10-VO_B)") (class "Default")
      (node (ref "IC10") (pin "6") (pinfunction "VO_B_6") (pintype "bidirectional"))
      (node (ref "U$2") (pin "S") (pinfunction "OUT_S") (pintype "bidirectional"))
    )
    (net (code "83") (name "Net-(IC10-V_ISO)") (class "Default")
      (node (ref "C7") (pin "1") (pinfunction "1_1") (pintype "passive"))
      (node (ref "IC10") (pin "8") (pinfunction "V_ISO_8") (pintype "bidirectional"))
    )
    (net (code "84") (name "Net-(L2-Pad2)") (class "Default")
      (node (ref "L2") (pin "2") (pinfunction "2_2") (pintype "passive"))
      (node (ref "U$5") (pin "12VOUT") (pinfunction "12VOUT_12VOUT") (pintype "bidirectional"))
    )
    (net (code "85") (name "Net-(U$3-OUT)") (class "Default")
      (node (ref "R2") (pin "2") (pinfunction "2_2") (pintype "passive"))
      (node (ref "U$3") (pin "S") (pinfunction "OUT_S") (pintype "bidirectional"))
    )
    (net (code "86") (name "Net-(U$4-OUT)") (class "Default")
      (node (ref "R3") (pin "2") (pinfunction "2_2") (pintype "passive"))
      (node (ref "U$4") (pin "S") (pinfunction "OUT_S") (pintype "bidirectional"))
    )
    (net (code "87") (name "Net-(U$6-P$7)") (class "Default")
      (node (ref "R7") (pin "2") (pinfunction "2_2") (pintype "passive"))
      (node (ref "U$6") (pin "P$17") (pinfunction "P$7_P$17") (pintype "bidirectional"))
    )
    (net (code "88") (name "Net-(U$6-P$9)") (class "Default")
      (node (ref "R6") (pin "2") (pinfunction "2_2") (pintype "passive"))
      (node (ref "U$6") (pin "P$19") (pinfunction "P$9_P$19") (pintype "bidirectional"))
    )
    (net (code "89") (name "Net-(U$8-2)") (class "Default")
      (node (ref "R1") (pin "2") (pinfunction "2_2") (pintype "passive"))
      (node (ref "U$8") (pin "P$2") (pinfunction "2_P$2") (pintype "bidirectional"))
    )
    (net (code "90") (name "VCC") (class "Default")
      (node (ref "C3") (pin "1") (pinfunction "1_1") (pintype "passive"))
      (node (ref "C4") (pin "1") (pinfunction "1_1") (pintype "passive"))
      (node (ref "C5") (pin "1") (pinfunction "1_1") (pintype "passive"))
      (node (ref "C8") (pin "1") (pinfunction "1_1") (pintype "passive"))
      (node (ref "C9") (pin "2") (pinfunction "2_2") (pintype "passive"))
      (node (ref "DUE_PWR") (pin "2") (pinfunction "2_2") (pintype "passive"))
      (node (ref "IC1") (pin "8") (pinfunction "CL1_8") (pintype "bidirectional"))
      (node (ref "IC2") (pin "8") (pinfunction "CL1_8") (pintype "bidirectional"))
      (node (ref "IC3") (pin "1") (pinfunction "VCC_1") (pintype "bidirectional"))
      (node (ref "IC4") (pin "1") (pinfunction "VCC_1") (pintype "bidirectional"))
      (node (ref "IC7") (pin "1") (pinfunction "VCC_1") (pintype "bidirectional"))
      (node (ref "IC8") (pin "1") (pinfunction "VCC_1") (pintype "bidirectional"))
      (node (ref "IC9") (pin "1") (pinfunction "VCC_1") (pintype "bidirectional"))
    )
    (net (code "91") (name "unconnected-(DUE_ALG-Pad1)") (class "Default")
      (node (ref "DUE_ALG") (pin "1") (pinfunction "1_1") (pintype "passive"))
    )
    (net (code "92") (name "unconnected-(DUE_ALG-Pad2)") (class "Default")
      (node (ref "DUE_ALG") (pin "2") (pinfunction "2_2") (pintype "passive"))
    )
    (net (code "93") (name "unconnected-(DUE_ALG-Pad3)") (class "Default")
      (node (ref "DUE_ALG") (pin "3") (pinfunction "3_3") (pintype "passive"))
    )
    (net (code "94") (name "unconnected-(DUE_ALG-Pad4)") (class "Default")
      (node (ref "DUE_ALG") (pin "4") (pinfunction "4_4") (pintype "passive"))
    )
    (net (code "95") (name "unconnected-(DUE_ALG-Pad5)") (class "Default")
      (node (ref "DUE_ALG") (pin "5") (pinfunction "5_5") (pintype "passive"))
    )
    (net (code "96") (name "unconnected-(DUE_ALG-Pad6)") (class "Default")
      (node (ref "DUE_ALG") (pin "6") (pinfunction "6_6") (pintype "passive"))
    )
    (net (code "97") (name "unconnected-(DUE_ALG-Pad7)") (class "Default")
      (node (ref "DUE_ALG") (pin "7") (pinfunction "7_7") (pintype "passive"))
    )
    (net (code "98") (name "unconnected-(DUE_ALG-Pad8)") (class "Default")
      (node (ref "DUE_ALG") (pin "8") (pinfunction "8_8") (pintype "passive"))
    )
    (net (code "99") (name "unconnected-(DUE_DIGITAL1-Pad1)") (class "Default")
      (node (ref "DUE_DIGITAL1") (pin "1") (pinfunction "1_1") (pintype "passive"))
    )
    (net (code "100") (name "unconnected-(DUE_DIGITAL1-Pad2)") (class "Default")
      (node (ref "DUE_DIGITAL1") (pin "2") (pinfunction "2_2") (pintype "passive"))
    )
    (net (code "101") (name "unconnected-(DUE_DIGITAL2-Pad7)") (class "Default")
      (node (ref "DUE_DIGITAL2") (pin "7") (pinfunction "7_7") (pintype "passive"))
    )
    (net (code "102") (name "unconnected-(DUE_DIGITAL2-Pad8)") (class "Default")
      (node (ref "DUE_DIGITAL2") (pin "8") (pinfunction "8_8") (pintype "passive"))
    )
    (net (code "103") (name "unconnected-(DUE_DIGITAL3-Pad1)") (class "Default")
      (node (ref "DUE_DIGITAL3") (pin "1") (pinfunction "1_1") (pintype "passive"))
    )
    (net (code "104") (name "unconnected-(DUE_DIGITAL3-Pad2)") (class "Default")
      (node (ref "DUE_DIGITAL3") (pin "2") (pinfunction "2_2") (pintype "passive"))
    )
    (net (code "105") (name "unconnected-(DUE_DIGITAL4-Pad1)") (class "Default")
      (node (ref "DUE_DIGITAL4") (pin "1") (pinfunction "1_1") (pintype "passive"))
    )
    (net (code "106") (name "unconnected-(DUE_DIGITAL4-Pad4)") (class "Default")
      (node (ref "DUE_DIGITAL4") (pin "4") (pinfunction "4_4") (pintype "passive"))
    )
    (net (code "107") (name "unconnected-(DUE_DIGITAL4-Pad7)") (class "Default")
      (node (ref "DUE_DIGITAL4") (pin "7") (pinfunction "7_7") (pintype "passive"))
    )
    (net (code "108") (name "unconnected-(DUE_DIGITAL4-Pad8)") (class "Default")
      (node (ref "DUE_DIGITAL4") (pin "8") (pinfunction "8_8") (pintype "passive"))
    )
    (net (code "109") (name "unconnected-(DUE_DIGITAL4-Pad16)") (class "Default")
      (node (ref "DUE_DIGITAL4") (pin "16") (pinfunction "16_16") (pintype "passive"))
    )
    (net (code "110") (name "unconnected-(DUE_DIGITAL4-Pad18)") (class "Default")
      (node (ref "DUE_DIGITAL4") (pin "18") (pinfunction "18_18") (pintype "passive"))
    )
    (net (code "111") (name "unconnected-(DUE_PWR-Pad1)") (class "Default")
      (node (ref "DUE_PWR") (pin "1") (pinfunction "1_1") (pintype "passive"))
    )
    (net (code "112") (name "unconnected-(DUE_PWR-Pad6)") (class "Default")
      (node (ref "DUE_PWR") (pin "6") (pinfunction "6_6") (pintype "passive"))
    )
    (net (code "113") (name "unconnected-(IC3-NC-Pad16)") (class "Default")
      (node (ref "IC3") (pin "16") (pinfunction "NC_16") (pintype "bidirectional"))
    )
    (net (code "114") (name "unconnected-(IC3-NC2-Pad13)") (class "Default")
      (node (ref "IC3") (pin "13") (pinfunction "NC2_13") (pintype "bidirectional"))
    )
    (net (code "115") (name "unconnected-(IC4-1IN-Pad3)") (class "Default")
      (node (ref "IC4") (pin "3") (pinfunction "1IN_3") (pintype "bidirectional"))
    )
    (net (code "116") (name "unconnected-(IC4-1OUT-Pad2)") (class "Default")
      (node (ref "IC4") (pin "2") (pinfunction "1OUT_2") (pintype "bidirectional"))
    )
    (net (code "117") (name "unconnected-(IC4-2IN-Pad5)") (class "Default")
      (node (ref "IC4") (pin "5") (pinfunction "2IN_5") (pintype "bidirectional"))
    )
    (net (code "118") (name "unconnected-(IC4-2OUT-Pad4)") (class "Default")
      (node (ref "IC4") (pin "4") (pinfunction "2OUT_4") (pintype "bidirectional"))
    )
    (net (code "119") (name "unconnected-(IC4-5IN-Pad11)") (class "Default")
      (node (ref "IC4") (pin "11") (pinfunction "5IN_11") (pintype "bidirectional"))
    )
    (net (code "120") (name "unconnected-(IC4-5OUT-Pad12)") (class "Default")
      (node (ref "IC4") (pin "12") (pinfunction "5OUT_12") (pintype "bidirectional"))
    )
    (net (code "121") (name "unconnected-(IC4-6IN-Pad14)") (class "Default")
      (node (ref "IC4") (pin "14") (pinfunction "6IN_14") (pintype "bidirectional"))
    )
    (net (code "122") (name "unconnected-(IC4-6OUT-Pad15)") (class "Default")
      (node (ref "IC4") (pin "15") (pinfunction "6OUT_15") (pintype "bidirectional"))
    )
    (net (code "123") (name "unconnected-(IC4-NC-Pad16)") (class "Default")
      (node (ref "IC4") (pin "16") (pinfunction "NC_16") (pintype "bidirectional"))
    )
    (net (code "124") (name "unconnected-(IC4-NC2-Pad13)") (class "Default")
      (node (ref "IC4") (pin "13") (pinfunction "NC2_13") (pintype "bidirectional"))
    )
    (net (code "125") (name "unconnected-(IC5-Pad13)") (class "Default")
      (node (ref "IC5") (pin "13") (pinfunction "13_13") (pintype "passive"))
    )
    (net (code "126") (name "unconnected-(ICSP-Pad1)") (class "Default")
      (node (ref "ICSP") (pin "1") (pinfunction "1_1") (pintype "passive"))
    )
    (net (code "127") (name "unconnected-(ICSP-Pad2)") (class "Default")
      (node (ref "ICSP") (pin "2") (pinfunction "2_2") (pintype "passive"))
    )
    (net (code "128") (name "unconnected-(ICSP-Pad5)") (class "Default")
      (node (ref "ICSP") (pin "5") (pinfunction "5_5") (pintype "passive"))
    )
    (net (code "129") (name "unconnected-(ICSP-Pad6)") (class "Default")
      (node (ref "ICSP") (pin "6") (pinfunction "6_6") (pintype "passive"))
    )
    (net (code "130") (name "unconnected-(PORT1-Pad2)") (class "Default")
      (node (ref "PORT1") (pin "2") (pinfunction "2_2") (pintype "bidirectional"))
    )
    (net (code "131") (name "unconnected-(PORT1-Pad8)") (class "Default")
      (node (ref "PORT1") (pin "8") (pinfunction "8_8") (pintype "bidirectional"))
    )
    (net (code "132") (name "unconnected-(PORT2-Pad2)") (class "Default")
      (node (ref "PORT2") (pin "2") (pinfunction "2_2") (pintype "bidirectional"))
    )
    (net (code "133") (name "unconnected-(PORT2-Pad8)") (class "Default")
      (node (ref "PORT2") (pin "8") (pinfunction "8_8") (pintype "bidirectional"))
    )
    (net (code "134") (name "unconnected-(PORT3-Pad2)") (class "Default")
      (node (ref "PORT3") (pin "2") (pinfunction "2_2") (pintype "bidirectional"))
    )
    (net (code "135") (name "unconnected-(PORT3-Pad8)") (class "Default")
      (node (ref "PORT3") (pin "8") (pinfunction "8_8") (pintype "bidirectional"))
    )
    (net (code "136") (name "unconnected-(PORT4-Pad2)") (class "Default")
      (node (ref "PORT4") (pin "2") (pinfunction "2_2") (pintype "bidirectional"))
    )
    (net (code "137") (name "unconnected-(PORT4-Pad8)") (class "Default")
      (node (ref "PORT4") (pin "8") (pinfunction "8_8") (pintype "bidirectional"))
    )
    (net (code "138") (name "unconnected-(PORT5-Pad2)") (class "Default")
      (node (ref "PORT5") (pin "2") (pinfunction "2_2") (pintype "bidirectional"))
    )
    (net (code "139") (name "unconnected-(PORT5-Pad8)") (class "Default")
      (node (ref "PORT5") (pin "8") (pinfunction "8_8") (pintype "bidirectional"))
    )
    (net (code "140") (name "unconnected-(PORT6-Pad2)") (class "Default")
      (node (ref "PORT6") (pin "2") (pinfunction "2_2") (pintype "bidirectional"))
    )
    (net (code "141") (name "unconnected-(PORT6-Pad8)") (class "Default")
      (node (ref "PORT6") (pin "8") (pinfunction "8_8") (pintype "bidirectional"))
    )
    (net (code "142") (name "unconnected-(PORT7-Pad2)") (class "Default")
      (node (ref "PORT7") (pin "2") (pinfunction "2_2") (pintype "bidirectional"))
    )
    (net (code "143") (name "unconnected-(PORT7-Pad8)") (class "Default")
      (node (ref "PORT7") (pin "8") (pinfunction "8_8") (pintype "bidirectional"))
    )
    (net (code "144") (name "unconnected-(PORT8-Pad2)") (class "Default")
      (node (ref "PORT8") (pin "2") (pinfunction "2_2") (pintype "bidirectional"))
    )
    (net (code "145") (name "unconnected-(PORT8-Pad8)") (class "Default")
      (node (ref "PORT8") (pin "8") (pinfunction "8_8") (pintype "bidirectional"))
    )
    (net (code "146") (name "unconnected-(SERIAL1-Pad5)") (class "Default")
      (node (ref "SERIAL1") (pin "5") (pinfunction "5_5") (pintype "bidirectional"))
    )
    (net (code "147") (name "unconnected-(SERIAL1-Pad6)") (class "Default")
      (node (ref "SERIAL1") (pin "6") (pinfunction "6_6") (pintype "bidirectional"))
    )
    (net (code "148") (name "unconnected-(SERIAL1-Pad7)") (class "Default")
      (node (ref "SERIAL1") (pin "7") (pinfunction "7_7") (pintype "bidirectional"))
    )
    (net (code "149") (name "unconnected-(SERIAL1-Pad8)") (class "Default")
      (node (ref "SERIAL1") (pin "8") (pinfunction "8_8") (pintype "bidirectional"))
    )
    (net (code "150") (name "unconnected-(SERIAL2-Pad5)") (class "Default")
      (node (ref "SERIAL2") (pin "5") (pinfunction "5_5") (pintype "bidirectional"))
    )
    (net (code "151") (name "unconnected-(SERIAL2-Pad6)") (class "Default")
      (node (ref "SERIAL2") (pin "6") (pinfunction "6_6") (pintype "bidirectional"))
    )
    (net (code "152") (name "unconnected-(SERIAL2-Pad7)") (class "Default")
      (node (ref "SERIAL2") (pin "7") (pinfunction "7_7") (pintype "bidirectional"))
    )
    (net (code "153") (name "unconnected-(SERIAL2-Pad8)") (class "Default")
      (node (ref "SERIAL2") (pin "8") (pinfunction "8_8") (pintype "bidirectional"))
    )
    (net (code "154") (name "unconnected-(SYNC-Pad5)") (class "Default")
      (node (ref "SYNC") (pin "5") (pinfunction "5_5") (pintype "bidirectional"))
    )
    (net (code "155") (name "unconnected-(SYNC-Pad6)") (class "Default")
      (node (ref "SYNC") (pin "6") (pinfunction "6_6") (pintype "bidirectional"))
    )
    (net (code "156") (name "unconnected-(SYNC-Pad7)") (class "Default")
      (node (ref "SYNC") (pin "7") (pinfunction "7_7") (pintype "bidirectional"))
    )
    (net (code "157") (name "unconnected-(SYNC-Pad8)") (class "Default")
      (node (ref "SYNC") (pin "8") (pinfunction "8_8") (pintype "bidirectional"))
    )
  )
)
